# SCS_Charger_RevA.net
KiCad netlist of a schematic drawn in Altium Designer
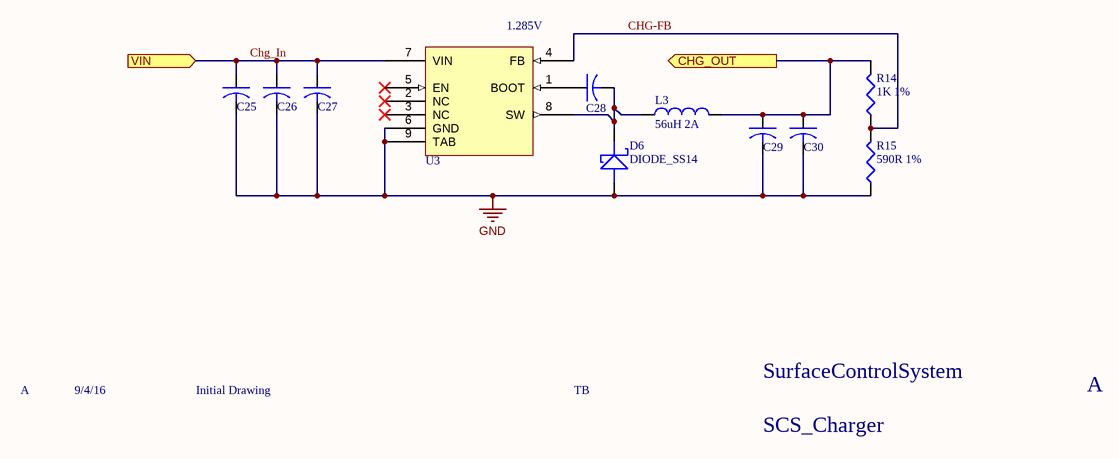
[diagram p0: SCS_Charger_RevA.SchDoc]

(export (version "E")
  (design (tool "Eeschema 10.0.6"))
  (components
    (comp (ref "C25")
      (value "10UF 25V")
      (footprint "1206")
      (description "CAP CER 10UF 25V 10% X5R 1206")
      (fields (field (name "MANUFACTURER") "Murata"))
      (libsource (lib "Caps") (part "CAP_10UF_25V_10%_1206"))
    )
    (comp (ref "C26")
      (value "10UF 25V")
      (footprint "1206")
      (description "CAP CER 10UF 25V 10% X5R 1206")
      (fields (field (name "MANUFACTURER") "Murata"))
      (libsource (lib "Caps") (part "CAP_10UF_25V_10%_1206"))
    )
    (comp (ref "C27")
      (value "100nF 50V")
      (footprint "0603")
      (description "CAP CER 100nF 50V 10% X7R 0603")
      (fields (field (name "MANUFACTURER") "Murata"))
      (libsource (lib "PowerDistributor") (part "CAP_100NF_50V_10%_0603"))
    )
    (comp (ref "C28")
      (value "10NF 50V")
      (footprint "0603")
      (description "CAP CER 10NF 50V 10% X7R 0603")
      (fields (field (name "MANUFACTURER") "Murata"))
      (libsource (lib "PowerDistributor") (part "CAP_10NF_50V_10%_0603"))
    )
    (comp (ref "C29")
      (value "10UF 25V")
      (footprint "1206")
      (description "CAP CER 10UF 25V 10% X5R 1206")
      (fields (field (name "MANUFACTURER") "Murata"))
      (libsource (lib "Caps") (part "CAP_10UF_25V_10%_1206"))
    )
    (comp (ref "C30")
      (value "10UF 25V")
      (footprint "1206")
      (description "CAP CER 10UF 25V 10% X5R 1206")
      (fields (field (name "MANUFACTURER") "Murata"))
      (libsource (lib "Caps") (part "CAP_10UF_25V_10%_1206"))
    )
    (comp (ref "D6")
      (value "DIODE_SS14")
      (footprint "DO-214AC")
      (description "Schottky Diode, 1A, 40V SS14")
      (fields (field (name "MANUFACTURER") "Fairchild"))
      (libsource (lib "PowerDistributor") (part "DIODE_SS14"))
    )
    (comp (ref "L3")
      (value "56uH 2A")
      (footprint "Wurth744771156")
      (description "FIXED IND 56UH 2.01A 110 MOHM")
      (fields (field (name "MANUFACTURER") "Wurth Electronics Inc"))
      (libsource (lib "PowerDistributor") (part "IND_56uH_2.01A"))
    )
    (comp (ref "R14")
      (value "1K 1%")
      (footprint "0603")
      (description "Resistor, 1K, 1%, 0603")
      (fields (field (name "MANUFACTURER") "Bourns Inc"))
      (libsource (lib "PowerDistributor") (part "RES_1K_1%_0603"))
    )
    (comp (ref "R15")
      (value "590R 1%")
      (footprint "0603")
      (description "Resistor, 590R, 1%, 0603")
      (fields (field (name "MANUFACTURER") "Bourns Inc"))
      (libsource (lib "PowerDistributor") (part "RES_590R_1%_0603"))
    )
    (comp (ref "U3")
      (value "Buck Reg")
      (footprint "PSOP-8")
      (description "IC REG BUCK 5V 1A 8SOPWRPAD")
      (fields (field (name "MANUFACTURER") "Texas Instruments"))
      (libsource (lib "PowerDistributor") (part "IC_REG_LM22675"))
    )
  )
  (nets
    (net (code "1") (name "/CHG-FB") (class "Default")
      (node (ref "R14") (pin "1") (pintype "passive"))
      (node (ref "R15") (pin "2") (pintype "passive"))
      (node (ref "U3") (pin "4") (pinfunction "FB_4") (pintype "input"))
    )
    (net (code "2") (name "/CHG_OUT") (class "Default")
      (node (ref "C29") (pin "1") (pinfunction "1_1") (pintype "passive"))
      (node (ref "C30") (pin "1") (pinfunction "1_1") (pintype "passive"))
      (node (ref "L3") (pin "2") (pinfunction "2_2") (pintype "passive"))
      (node (ref "R14") (pin "2") (pintype "passive"))
    )
    (net (code "3") (name "/Chg_In") (class "Default")
      (node (ref "C25") (pin "1") (pinfunction "1_1") (pintype "passive"))
      (node (ref "C26") (pin "1") (pinfunction "1_1") (pintype "passive"))
      (node (ref "C27") (pin "1") (pinfunction "1_1") (pintype "passive"))
      (node (ref "U3") (pin "7") (pinfunction "VIN_7") (pintype "power_in"))
    )
    (net (code "4") (name "GND") (class "Default")
      (node (ref "C25") (pin "2") (pinfunction "2_2") (pintype "passive"))
      (node (ref "C26") (pin "2") (pinfunction "2_2") (pintype "passive"))
      (node (ref "C27") (pin "2") (pinfunction "2_2") (pintype "passive"))
      (node (ref "C29") (pin "2") (pinfunction "2_2") (pintype "passive"))
      (node (ref "C30") (pin "2") (pinfunction "2_2") (pintype "passive"))
      (node (ref "D6") (pin "A") (pinfunction "A_A") (pintype "passive"))
      (node (ref "R15") (pin "1") (pintype "passive"))
      (node (ref "U3") (pin "6") (pinfunction "GND_6") (pintype "power_in"))
      (node (ref "U3") (pin "9") (pinfunction "TAB_9") (pintype "power_in"))
    )
    (net (code "5") (name "Net-(U3-BOOT)") (class "Default")
      (node (ref "C28") (pin "1") (pinfunction "1_1") (pintype "passive"))
      (node (ref "U3") (pin "1") (pinfunction "BOOT_1") (pintype "input"))
    )
    (net (code "6") (name "Net-(U3-SW)") (class "Default")
      (node (ref "C28") (pin "2") (pinfunction "2_2") (pintype "passive"))
      (node (ref "D6") (pin "K") (pinfunction "K_K") (pintype "passive"))
      (node (ref "L3") (pin "1") (pinfunction "1_1") (pintype "passive"))
      (node (ref "U3") (pin "8") (pinfunction "SW_8") (pintype "output"))
    )
    (net (code "7") (name "unconnected-(U3-EN-Pad5)") (class "Default")
      (node (ref "U3") (pin "5") (pinfunction "EN_5") (pintype "input+no_connect"))
    )
    (net (code "8") (name "unconnected-(U3-NC-Pad2)") (class "Default")
      (node (ref "U3") (pin "2") (pinfunction "NC_2") (pintype "tri_state+no_connect"))
    )
    (net (code "9") (name "unconnected-(U3-NC-Pad3)") (class "Default")
      (node (ref "U3") (pin "3") (pinfunction "NC_3") (pintype "tri_state+no_connect"))
    )
  )
)
